# 88LM_Schematic.net
KiCad netlist of a schematic drawn in Altium Designer
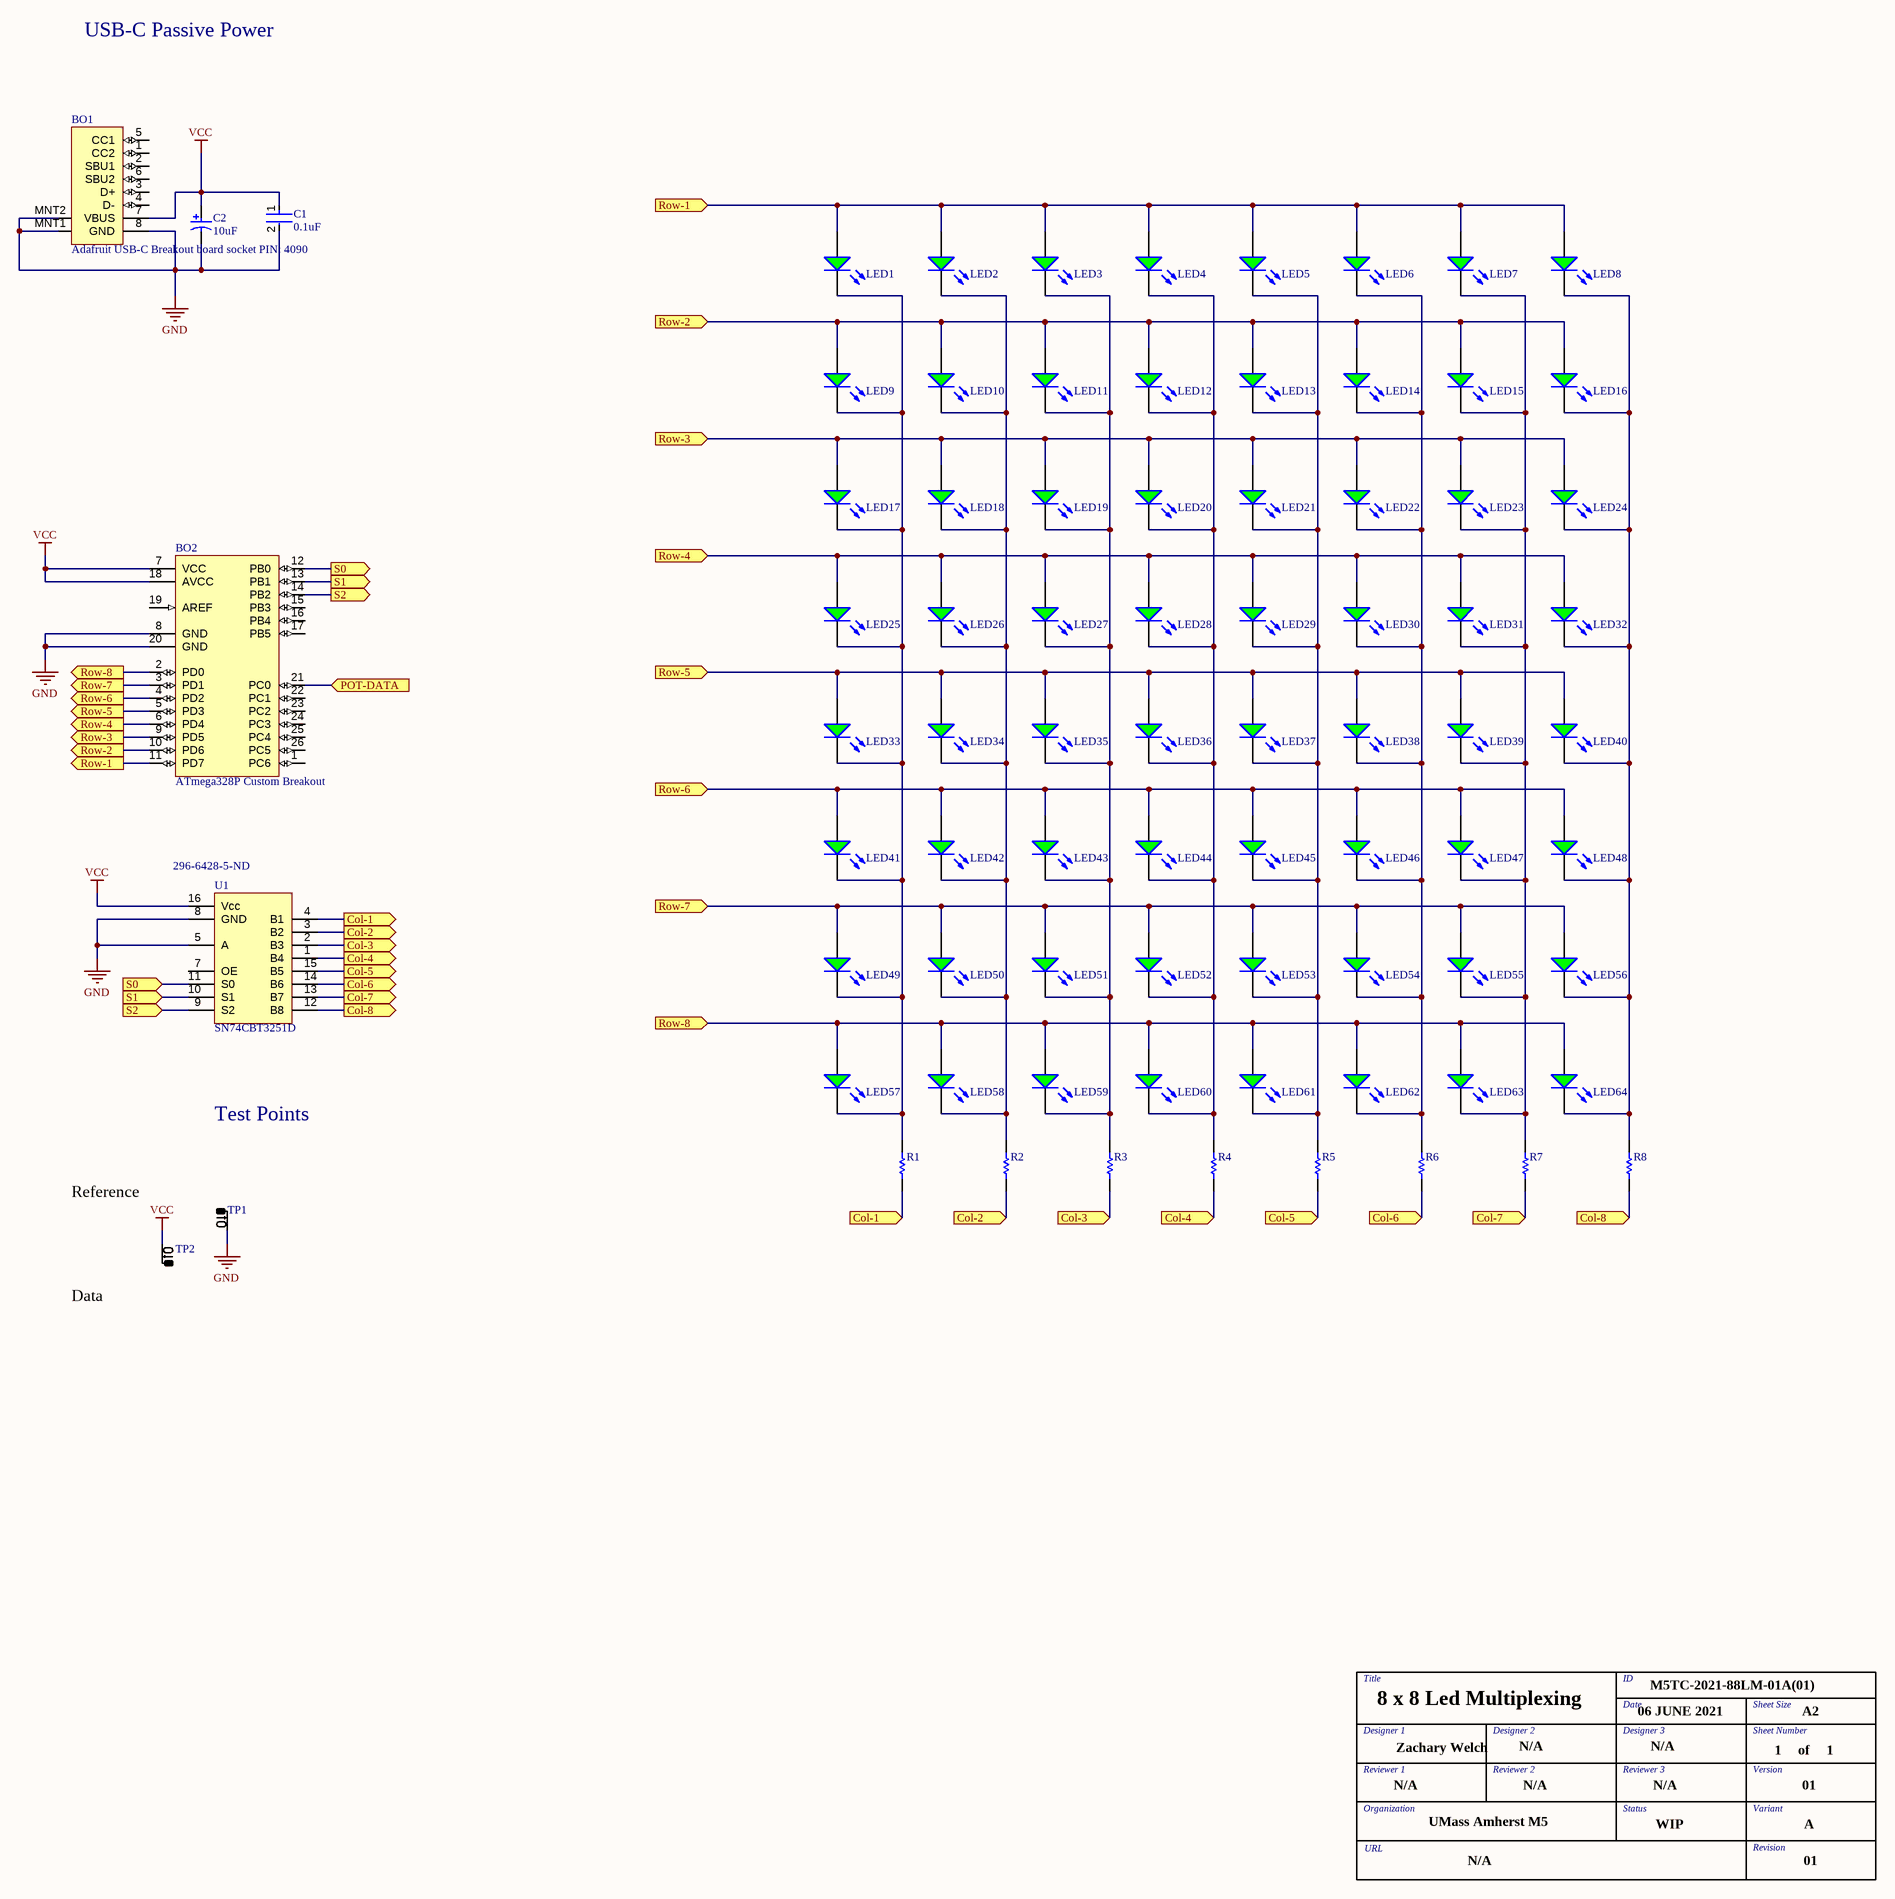
[diagram p0: 88LM Schematic.SchDoc]

(export (version "E")
  (design (tool "Eeschema 10.0.6"))
  (components
    (comp (ref "BO1")
      (value "Adafruit USB-C Breakout board socket PIN: 4090")
      (footprint "Adafruit USB-C Breakout")
      (description "https://www.adafruit.com/product/4090")
      (libsource (lib "Master Schematic Library") (part "Adafruit USB-C Breakout"))
    )
    (comp (ref "BO2")
      (value "ATmega328P Custom Breakout")
      (footprint "328P-BOB")
      (description "Custom Breakout Board for 328P-PU")
      (libsource (lib "Master Schematic Library") (part "328P-BOB"))
    )
    (comp (ref "C1")
      (value "0.1uF")
      (footprint "FP-C0603-CJ-MFG")
      (description "CAP CER 0.1UF 50V X7R 0603")
      (fields (field (name "MANUFACTURER PART NUMBER") "C0603X104K5RACTU") (field (name "VOLTAGE") "50V"))
      (libsource (lib "Altium Content Vault") (part "11868f565c42a9108669ba33697ecf6"))
    )
    (comp (ref "C2")
      (value "10uF")
      (footprint "KEMT-A-3216-18-2_M")
      (description "Capacitor, Tantalum, 10 uF, +/- 10%, 10 V, -55 to 125 degC, 2-Pin SMD (1206), RoHS, Tape and Reel")
      (fields (field (name "TOLERANCE") "±10%") (field (name "MANUFACTURER") "Kemet"))
      (libsource (lib "Altium Content Vault") (part "CAP-P-2"))
    )
    (comp (ref "LED1")
      (value "HLMP-4740")
      (footprint "AVAG-HLMP-4740")
      (description "T-1 3/4 (5 mm) Low Current LED Lamp, Green, 1.9 V, -20 to 100 degC, 2-Pin THD, RoHS, Bulk")
      (fields (field (name "MANUFACTURER") "AvagoTechnologies"))
      (libsource (lib "Altium Content Vault") (part "LED-GREEN-AK-2"))
    )
    (comp (ref "LED2")
      (value "HLMP-4740")
      (footprint "AVAG-HLMP-4740")
      (description "T-1 3/4 (5 mm) Low Current LED Lamp, Green, 1.9 V, -20 to 100 degC, 2-Pin THD, RoHS, Bulk")
      (fields (field (name "MANUFACTURER") "AvagoTechnologies"))
      (libsource (lib "Altium Content Vault") (part "LED-GREEN-AK-2"))
    )
    (comp (ref "LED3")
      (value "HLMP-4740")
      (footprint "AVAG-HLMP-4740")
      (description "T-1 3/4 (5 mm) Low Current LED Lamp, Green, 1.9 V, -20 to 100 degC, 2-Pin THD, RoHS, Bulk")
      (fields (field (name "MANUFACTURER") "AvagoTechnologies"))
      (libsource (lib "Altium Content Vault") (part "LED-GREEN-AK-2"))
    )
    (comp (ref "LED4")
      (value "HLMP-4740")
      (footprint "AVAG-HLMP-4740")
      (description "T-1 3/4 (5 mm) Low Current LED Lamp, Green, 1.9 V, -20 to 100 degC, 2-Pin THD, RoHS, Bulk")
      (fields (field (name "MANUFACTURER") "AvagoTechnologies"))
      (libsource (lib "Altium Content Vault") (part "LED-GREEN-AK-2"))
    )
    (comp (ref "LED5")
      (value "HLMP-4740")
      (footprint "AVAG-HLMP-4740")
      (description "T-1 3/4 (5 mm) Low Current LED Lamp, Green, 1.9 V, -20 to 100 degC, 2-Pin THD, RoHS, Bulk")
      (fields (field (name "MANUFACTURER") "AvagoTechnologies"))
      (libsource (lib "Altium Content Vault") (part "LED-GREEN-AK-2"))
    )
    (comp (ref "LED6")
      (value "HLMP-4740")
      (footprint "AVAG-HLMP-4740")
      (description "T-1 3/4 (5 mm) Low Current LED Lamp, Green, 1.9 V, -20 to 100 degC, 2-Pin THD, RoHS, Bulk")
      (fields (field (name "MANUFACTURER") "AvagoTechnologies"))
      (libsource (lib "Altium Content Vault") (part "LED-GREEN-AK-2"))
    )
    (comp (ref "LED7")
      (value "HLMP-4740")
      (footprint "AVAG-HLMP-4740")
      (description "T-1 3/4 (5 mm) Low Current LED Lamp, Green, 1.9 V, -20 to 100 degC, 2-Pin THD, RoHS, Bulk")
      (fields (field (name "MANUFACTURER") "AvagoTechnologies"))
      (libsource (lib "Altium Content Vault") (part "LED-GREEN-AK-2"))
    )
    (comp (ref "LED8")
      (value "HLMP-4740")
      (footprint "AVAG-HLMP-4740")
      (description "T-1 3/4 (5 mm) Low Current LED Lamp, Green, 1.9 V, -20 to 100 degC, 2-Pin THD, RoHS, Bulk")
      (fields (field (name "MANUFACTURER") "AvagoTechnologies"))
      (libsource (lib "Altium Content Vault") (part "LED-GREEN-AK-2"))
    )
    (comp (ref "LED9")
      (value "HLMP-4740")
      (footprint "AVAG-HLMP-4740")
      (description "T-1 3/4 (5 mm) Low Current LED Lamp, Green, 1.9 V, -20 to 100 degC, 2-Pin THD, RoHS, Bulk")
      (fields (field (name "MANUFACTURER") "AvagoTechnologies"))
      (libsource (lib "Altium Content Vault") (part "LED-GREEN-AK-2"))
    )
    (comp (ref "LED10")
      (value "HLMP-4740")
      (footprint "AVAG-HLMP-4740")
      (description "T-1 3/4 (5 mm) Low Current LED Lamp, Green, 1.9 V, -20 to 100 degC, 2-Pin THD, RoHS, Bulk")
      (fields (field (name "MANUFACTURER") "AvagoTechnologies"))
      (libsource (lib "Altium Content Vault") (part "LED-GREEN-AK-2"))
    )
    (comp (ref "LED11")
      (value "HLMP-4740")
      (footprint "AVAG-HLMP-4740")
      (description "T-1 3/4 (5 mm) Low Current LED Lamp, Green, 1.9 V, -20 to 100 degC, 2-Pin THD, RoHS, Bulk")
      (fields (field (name "MANUFACTURER") "AvagoTechnologies"))
      (libsource (lib "Altium Content Vault") (part "LED-GREEN-AK-2"))
    )
    (comp (ref "LED12")
      (value "HLMP-4740")
      (footprint "AVAG-HLMP-4740")
      (description "T-1 3/4 (5 mm) Low Current LED Lamp, Green, 1.9 V, -20 to 100 degC, 2-Pin THD, RoHS, Bulk")
      (fields (field (name "MANUFACTURER") "AvagoTechnologies"))
      (libsource (lib "Altium Content Vault") (part "LED-GREEN-AK-2"))
    )
    (comp (ref "LED13")
      (value "HLMP-4740")
      (footprint "AVAG-HLMP-4740")
      (description "T-1 3/4 (5 mm) Low Current LED Lamp, Green, 1.9 V, -20 to 100 degC, 2-Pin THD, RoHS, Bulk")
      (fields (field (name "MANUFACTURER") "AvagoTechnologies"))
      (libsource (lib "Altium Content Vault") (part "LED-GREEN-AK-2"))
    )
    (comp (ref "LED14")
      (value "HLMP-4740")
      (footprint "AVAG-HLMP-4740")
      (description "T-1 3/4 (5 mm) Low Current LED Lamp, Green, 1.9 V, -20 to 100 degC, 2-Pin THD, RoHS, Bulk")
      (fields (field (name "MANUFACTURER") "AvagoTechnologies"))
      (libsource (lib "Altium Content Vault") (part "LED-GREEN-AK-2"))
    )
    (comp (ref "LED15")
      (value "HLMP-4740")
      (footprint "AVAG-HLMP-4740")
      (description "T-1 3/4 (5 mm) Low Current LED Lamp, Green, 1.9 V, -20 to 100 degC, 2-Pin THD, RoHS, Bulk")
      (fields (field (name "MANUFACTURER") "AvagoTechnologies"))
      (libsource (lib "Altium Content Vault") (part "LED-GREEN-AK-2"))
    )
    (comp (ref "LED16")
      (value "HLMP-4740")
      (footprint "AVAG-HLMP-4740")
      (description "T-1 3/4 (5 mm) Low Current LED Lamp, Green, 1.9 V, -20 to 100 degC, 2-Pin THD, RoHS, Bulk")
      (fields (field (name "MANUFACTURER") "AvagoTechnologies"))
      (libsource (lib "Altium Content Vault") (part "LED-GREEN-AK-2"))
    )
    (comp (ref "LED17")
      (value "HLMP-4740")
      (footprint "AVAG-HLMP-4740")
      (description "T-1 3/4 (5 mm) Low Current LED Lamp, Green, 1.9 V, -20 to 100 degC, 2-Pin THD, RoHS, Bulk")
      (fields (field (name "MANUFACTURER") "AvagoTechnologies"))
      (libsource (lib "Altium Content Vault") (part "LED-GREEN-AK-2"))
    )
    (comp (ref "LED18")
      (value "HLMP-4740")
      (footprint "AVAG-HLMP-4740")
      (description "T-1 3/4 (5 mm) Low Current LED Lamp, Green, 1.9 V, -20 to 100 degC, 2-Pin THD, RoHS, Bulk")
      (fields (field (name "MANUFACTURER") "AvagoTechnologies"))
      (libsource (lib "Altium Content Vault") (part "LED-GREEN-AK-2"))
    )
    (comp (ref "LED19")
      (value "HLMP-4740")
      (footprint "AVAG-HLMP-4740")
      (description "T-1 3/4 (5 mm) Low Current LED Lamp, Green, 1.9 V, -20 to 100 degC, 2-Pin THD, RoHS, Bulk")
      (fields (field (name "MANUFACTURER") "AvagoTechnologies"))
      (libsource (lib "Altium Content Vault") (part "LED-GREEN-AK-2"))
    )
    (comp (ref "LED20")
      (value "HLMP-4740")
      (footprint "AVAG-HLMP-4740")
      (description "T-1 3/4 (5 mm) Low Current LED Lamp, Green, 1.9 V, -20 to 100 degC, 2-Pin THD, RoHS, Bulk")
      (fields (field (name "MANUFACTURER") "AvagoTechnologies"))
      (libsource (lib "Altium Content Vault") (part "LED-GREEN-AK-2"))
    )
    (comp (ref "LED21")
      (value "HLMP-4740")
      (footprint "AVAG-HLMP-4740")
      (description "T-1 3/4 (5 mm) Low Current LED Lamp, Green, 1.9 V, -20 to 100 degC, 2-Pin THD, RoHS, Bulk")
      (fields (field (name "MANUFACTURER") "AvagoTechnologies"))
      (libsource (lib "Altium Content Vault") (part "LED-GREEN-AK-2"))
    )
    (comp (ref "LED22")
      (value "HLMP-4740")
      (footprint "AVAG-HLMP-4740")
      (description "T-1 3/4 (5 mm) Low Current LED Lamp, Green, 1.9 V, -20 to 100 degC, 2-Pin THD, RoHS, Bulk")
      (fields (field (name "MANUFACTURER") "AvagoTechnologies"))
      (libsource (lib "Altium Content Vault") (part "LED-GREEN-AK-2"))
    )
    (comp (ref "LED23")
      (value "HLMP-4740")
      (footprint "AVAG-HLMP-4740")
      (description "T-1 3/4 (5 mm) Low Current LED Lamp, Green, 1.9 V, -20 to 100 degC, 2-Pin THD, RoHS, Bulk")
      (fields (field (name "MANUFACTURER") "AvagoTechnologies"))
      (libsource (lib "Altium Content Vault") (part "LED-GREEN-AK-2"))
    )
    (comp (ref "LED24")
      (value "HLMP-4740")
      (footprint "AVAG-HLMP-4740")
      (description "T-1 3/4 (5 mm) Low Current LED Lamp, Green, 1.9 V, -20 to 100 degC, 2-Pin THD, RoHS, Bulk")
      (fields (field (name "MANUFACTURER") "AvagoTechnologies"))
      (libsource (lib "Altium Content Vault") (part "LED-GREEN-AK-2"))
    )
    (comp (ref "LED25")
      (value "HLMP-4740")
      (footprint "AVAG-HLMP-4740")
      (description "T-1 3/4 (5 mm) Low Current LED Lamp, Green, 1.9 V, -20 to 100 degC, 2-Pin THD, RoHS, Bulk")
      (fields (field (name "MANUFACTURER") "AvagoTechnologies"))
      (libsource (lib "Altium Content Vault") (part "LED-GREEN-AK-2"))
    )
    (comp (ref "LED26")
      (value "HLMP-4740")
      (footprint "AVAG-HLMP-4740")
      (description "T-1 3/4 (5 mm) Low Current LED Lamp, Green, 1.9 V, -20 to 100 degC, 2-Pin THD, RoHS, Bulk")
      (fields (field (name "MANUFACTURER") "AvagoTechnologies"))
      (libsource (lib "Altium Content Vault") (part "LED-GREEN-AK-2"))
    )
    (comp (ref "LED27")
      (value "HLMP-4740")
      (footprint "AVAG-HLMP-4740")
      (description "T-1 3/4 (5 mm) Low Current LED Lamp, Green, 1.9 V, -20 to 100 degC, 2-Pin THD, RoHS, Bulk")
      (fields (field (name "MANUFACTURER") "AvagoTechnologies"))
      (libsource (lib "Altium Content Vault") (part "LED-GREEN-AK-2"))
    )
    (comp (ref "LED28")
      (value "HLMP-4740")
      (footprint "AVAG-HLMP-4740")
      (description "T-1 3/4 (5 mm) Low Current LED Lamp, Green, 1.9 V, -20 to 100 degC, 2-Pin THD, RoHS, Bulk")
      (fields (field (name "MANUFACTURER") "AvagoTechnologies"))
      (libsource (lib "Altium Content Vault") (part "LED-GREEN-AK-2"))
    )
    (comp (ref "LED29")
      (value "HLMP-4740")
      (footprint "AVAG-HLMP-4740")
      (description "T-1 3/4 (5 mm) Low Current LED Lamp, Green, 1.9 V, -20 to 100 degC, 2-Pin THD, RoHS, Bulk")
      (fields (field (name "MANUFACTURER") "AvagoTechnologies"))
      (libsource (lib "Altium Content Vault") (part "LED-GREEN-AK-2"))
    )
    (comp (ref "LED30")
      (value "HLMP-4740")
      (footprint "AVAG-HLMP-4740")
      (description "T-1 3/4 (5 mm) Low Current LED Lamp, Green, 1.9 V, -20 to 100 degC, 2-Pin THD, RoHS, Bulk")
      (fields (field (name "MANUFACTURER") "AvagoTechnologies"))
      (libsource (lib "Altium Content Vault") (part "LED-GREEN-AK-2"))
    )
    (comp (ref "LED31")
      (value "HLMP-4740")
      (footprint "AVAG-HLMP-4740")
      (description "T-1 3/4 (5 mm) Low Current LED Lamp, Green, 1.9 V, -20 to 100 degC, 2-Pin THD, RoHS, Bulk")
      (fields (field (name "MANUFACTURER") "AvagoTechnologies"))
      (libsource (lib "Altium Content Vault") (part "LED-GREEN-AK-2"))
    )
    (comp (ref "LED32")
      (value "HLMP-4740")
      (footprint "AVAG-HLMP-4740")
      (description "T-1 3/4 (5 mm) Low Current LED Lamp, Green, 1.9 V, -20 to 100 degC, 2-Pin THD, RoHS, Bulk")
      (fields (field (name "MANUFACTURER") "AvagoTechnologies"))
      (libsource (lib "Altium Content Vault") (part "LED-GREEN-AK-2"))
    )
    (comp (ref "LED33")
      (value "HLMP-4740")
      (footprint "AVAG-HLMP-4740")
      (description "T-1 3/4 (5 mm) Low Current LED Lamp, Green, 1.9 V, -20 to 100 degC, 2-Pin THD, RoHS, Bulk")
      (fields (field (name "MANUFACTURER") "AvagoTechnologies"))
      (libsource (lib "Altium Content Vault") (part "LED-GREEN-AK-2"))
    )
    (comp (ref "LED34")
      (value "HLMP-4740")
      (footprint "AVAG-HLMP-4740")
      (description "T-1 3/4 (5 mm) Low Current LED Lamp, Green, 1.9 V, -20 to 100 degC, 2-Pin THD, RoHS, Bulk")
      (fields (field (name "MANUFACTURER") "AvagoTechnologies"))
      (libsource (lib "Altium Content Vault") (part "LED-GREEN-AK-2"))
    )
    (comp (ref "LED35")
      (value "HLMP-4740")
      (footprint "AVAG-HLMP-4740")
      (description "T-1 3/4 (5 mm) Low Current LED Lamp, Green, 1.9 V, -20 to 100 degC, 2-Pin THD, RoHS, Bulk")
      (fields (field (name "MANUFACTURER") "AvagoTechnologies"))
      (libsource (lib "Altium Content Vault") (part "LED-GREEN-AK-2"))
    )
    (comp (ref "LED36")
      (value "HLMP-4740")
      (footprint "AVAG-HLMP-4740")
      (description "T-1 3/4 (5 mm) Low Current LED Lamp, Green, 1.9 V, -20 to 100 degC, 2-Pin THD, RoHS, Bulk")
      (fields (field (name "MANUFACTURER") "AvagoTechnologies"))
      (libsource (lib "Altium Content Vault") (part "LED-GREEN-AK-2"))
    )
    (comp (ref "LED37")
      (value "HLMP-4740")
      (footprint "AVAG-HLMP-4740")
      (description "T-1 3/4 (5 mm) Low Current LED Lamp, Green, 1.9 V, -20 to 100 degC, 2-Pin THD, RoHS, Bulk")
      (fields (field (name "MANUFACTURER") "AvagoTechnologies"))
      (libsource (lib "Altium Content Vault") (part "LED-GREEN-AK-2"))
    )
    (comp (ref "LED38")
      (value "HLMP-4740")
      (footprint "AVAG-HLMP-4740")
      (description "T-1 3/4 (5 mm) Low Current LED Lamp, Green, 1.9 V, -20 to 100 degC, 2-Pin THD, RoHS, Bulk")
      (fields (field (name "MANUFACTURER") "AvagoTechnologies"))
      (libsource (lib "Altium Content Vault") (part "LED-GREEN-AK-2"))
    )
    (comp (ref "LED39")
      (value "HLMP-4740")
      (footprint "AVAG-HLMP-4740")
      (description "T-1 3/4 (5 mm) Low Current LED Lamp, Green, 1.9 V, -20 to 100 degC, 2-Pin THD, RoHS, Bulk")
      (fields (field (name "MANUFACTURER") "AvagoTechnologies"))
      (libsource (lib "Altium Content Vault") (part "LED-GREEN-AK-2"))
    )
    (comp (ref "LED40")
      (value "HLMP-4740")
      (footprint "AVAG-HLMP-4740")
      (description "T-1 3/4 (5 mm) Low Current LED Lamp, Green, 1.9 V, -20 to 100 degC, 2-Pin THD, RoHS, Bulk")
      (fields (field (name "MANUFACTURER") "AvagoTechnologies"))
      (libsource (lib "Altium Content Vault") (part "LED-GREEN-AK-2"))
    )
    (comp (ref "LED41")
      (value "HLMP-4740")
      (footprint "AVAG-HLMP-4740")
      (description "T-1 3/4 (5 mm) Low Current LED Lamp, Green, 1.9 V, -20 to 100 degC, 2-Pin THD, RoHS, Bulk")
      (fields (field (name "MANUFACTURER") "AvagoTechnologies"))
      (libsource (lib "Altium Content Vault") (part "LED-GREEN-AK-2"))
    )
    (comp (ref "LED42")
      (value "HLMP-4740")
      (footprint "AVAG-HLMP-4740")
      (description "T-1 3/4 (5 mm) Low Current LED Lamp, Green, 1.9 V, -20 to 100 degC, 2-Pin THD, RoHS, Bulk")
      (fields (field (name "MANUFACTURER") "AvagoTechnologies"))
      (libsource (lib "Altium Content Vault") (part "LED-GREEN-AK-2"))
    )
    (comp (ref "LED43")
      (value "HLMP-4740")
      (footprint "AVAG-HLMP-4740")
      (description "T-1 3/4 (5 mm) Low Current LED Lamp, Green, 1.9 V, -20 to 100 degC, 2-Pin THD, RoHS, Bulk")
      (fields (field (name "MANUFACTURER") "AvagoTechnologies"))
      (libsource (lib "Altium Content Vault") (part "LED-GREEN-AK-2"))
    )
    (comp (ref "LED44")
      (value "HLMP-4740")
      (footprint "AVAG-HLMP-4740")
      (description "T-1 3/4 (5 mm) Low Current LED Lamp, Green, 1.9 V, -20 to 100 degC, 2-Pin THD, RoHS, Bulk")
      (fields (field (name "MANUFACTURER") "AvagoTechnologies"))
      (libsource (lib "Altium Content Vault") (part "LED-GREEN-AK-2"))
    )
    (comp (ref "LED45")
      (value "HLMP-4740")
      (footprint "AVAG-HLMP-4740")
      (description "T-1 3/4 (5 mm) Low Current LED Lamp, Green, 1.9 V, -20 to 100 degC, 2-Pin THD, RoHS, Bulk")
      (fields (field (name "MANUFACTURER") "AvagoTechnologies"))
      (libsource (lib "Altium Content Vault") (part "LED-GREEN-AK-2"))
    )
    (comp (ref "LED46")
      (value "HLMP-4740")
      (footprint "AVAG-HLMP-4740")
      (description "T-1 3/4 (5 mm) Low Current LED Lamp, Green, 1.9 V, -20 to 100 degC, 2-Pin THD, RoHS, Bulk")
      (fields (field (name "MANUFACTURER") "AvagoTechnologies"))
      (libsource (lib "Altium Content Vault") (part "LED-GREEN-AK-2"))
    )
    (comp (ref "LED47")
      (value "HLMP-4740")
      (footprint "AVAG-HLMP-4740")
      (description "T-1 3/4 (5 mm) Low Current LED Lamp, Green, 1.9 V, -20 to 100 degC, 2-Pin THD, RoHS, Bulk")
      (fields (field (name "MANUFACTURER") "AvagoTechnologies"))
      (libsource (lib "Altium Content Vault") (part "LED-GREEN-AK-2"))
    )
    (comp (ref "LED48")
      (value "HLMP-4740")
      (footprint "AVAG-HLMP-4740")
      (description "T-1 3/4 (5 mm) Low Current LED Lamp, Green, 1.9 V, -20 to 100 degC, 2-Pin THD, RoHS, Bulk")
      (fields (field (name "MANUFACTURER") "AvagoTechnologies"))
      (libsource (lib "Altium Content Vault") (part "LED-GREEN-AK-2"))
    )
    (comp (ref "LED49")
      (value "HLMP-4740")
      (footprint "AVAG-HLMP-4740")
      (description "T-1 3/4 (5 mm) Low Current LED Lamp, Green, 1.9 V, -20 to 100 degC, 2-Pin THD, RoHS, Bulk")
      (fields (field (name "MANUFACTURER") "AvagoTechnologies"))
      (libsource (lib "Altium Content Vault") (part "LED-GREEN-AK-2"))
    )
    (comp (ref "LED50")
      (value "HLMP-4740")
      (footprint "AVAG-HLMP-4740")
      (description "T-1 3/4 (5 mm) Low Current LED Lamp, Green, 1.9 V, -20 to 100 degC, 2-Pin THD, RoHS, Bulk")
      (fields (field (name "MANUFACTURER") "AvagoTechnologies"))
      (libsource (lib "Altium Content Vault") (part "LED-GREEN-AK-2"))
    )
    (comp (ref "LED51")
      (value "HLMP-4740")
      (footprint "AVAG-HLMP-4740")
      (description "T-1 3/4 (5 mm) Low Current LED Lamp, Green, 1.9 V, -20 to 100 degC, 2-Pin THD, RoHS, Bulk")
      (fields (field (name "MANUFACTURER") "AvagoTechnologies"))
      (libsource (lib "Altium Content Vault") (part "LED-GREEN-AK-2"))
    )
    (comp (ref "LED52")
      (value "HLMP-4740")
      (footprint "AVAG-HLMP-4740")
      (description "T-1 3/4 (5 mm) Low Current LED Lamp, Green, 1.9 V, -20 to 100 degC, 2-Pin THD, RoHS, Bulk")
      (fields (field (name "MANUFACTURER") "AvagoTechnologies"))
      (libsource (lib "Altium Content Vault") (part "LED-GREEN-AK-2"))
    )
    (comp (ref "LED53")
      (value "HLMP-4740")
      (footprint "AVAG-HLMP-4740")
      (description "T-1 3/4 (5 mm) Low Current LED Lamp, Green, 1.9 V, -20 to 100 degC, 2-Pin THD, RoHS, Bulk")
      (fields (field (name "MANUFACTURER") "AvagoTechnologies"))
      (libsource (lib "Altium Content Vault") (part "LED-GREEN-AK-2"))
    )
    (comp (ref "LED54")
      (value "HLMP-4740")
      (footprint "AVAG-HLMP-4740")
      (description "T-1 3/4 (5 mm) Low Current LED Lamp, Green, 1.9 V, -20 to 100 degC, 2-Pin THD, RoHS, Bulk")
      (fields (field (name "MANUFACTURER") "AvagoTechnologies"))
      (libsource (lib "Altium Content Vault") (part "LED-GREEN-AK-2"))
    )
    (comp (ref "LED55")
      (value "HLMP-4740")
      (footprint "AVAG-HLMP-4740")
      (description "T-1 3/4 (5 mm) Low Current LED Lamp, Green, 1.9 V, -20 to 100 degC, 2-Pin THD, RoHS, Bulk")
      (fields (field (name "MANUFACTURER") "AvagoTechnologies"))
      (libsource (lib "Altium Content Vault") (part "LED-GREEN-AK-2"))
    )
    (comp (ref "LED56")
      (value "HLMP-4740")
      (footprint "AVAG-HLMP-4740")
      (description "T-1 3/4 (5 mm) Low Current LED Lamp, Green, 1.9 V, -20 to 100 degC, 2-Pin THD, RoHS, Bulk")
      (fields (field (name "MANUFACTURER") "AvagoTechnologies"))
      (libsource (lib "Altium Content Vault") (part "LED-GREEN-AK-2"))
    )
    (comp (ref "LED57")
      (value "HLMP-4740")
      (footprint "AVAG-HLMP-4740")
      (description "T-1 3/4 (5 mm) Low Current LED Lamp, Green, 1.9 V, -20 to 100 degC, 2-Pin THD, RoHS, Bulk")
      (fields (field (name "MANUFACTURER") "AvagoTechnologies"))
      (libsource (lib "Altium Content Vault") (part "LED-GREEN-AK-2"))
    )
    (comp (ref "LED58")
      (value "HLMP-4740")
      (footprint "AVAG-HLMP-4740")
      (description "T-1 3/4 (5 mm) Low Current LED Lamp, Green, 1.9 V, -20 to 100 degC, 2-Pin THD, RoHS, Bulk")
      (fields (field (name "MANUFACTURER") "AvagoTechnologies"))
      (libsource (lib "Altium Content Vault") (part "LED-GREEN-AK-2"))
    )
    (comp (ref "LED59")
      (value "HLMP-4740")
      (footprint "AVAG-HLMP-4740")
      (description "T-1 3/4 (5 mm) Low Current LED Lamp, Green, 1.9 V, -20 to 100 degC, 2-Pin THD, RoHS, Bulk")
      (fields (field (name "MANUFACTURER") "AvagoTechnologies"))
      (libsource (lib "Altium Content Vault") (part "LED-GREEN-AK-2"))
    )
    (comp (ref "LED60")
      (value "HLMP-4740")
      (footprint "AVAG-HLMP-4740")
      (description "T-1 3/4 (5 mm) Low Current LED Lamp, Green, 1.9 V, -20 to 100 degC, 2-Pin THD, RoHS, Bulk")
      (fields (field (name "MANUFACTURER") "AvagoTechnologies"))
      (libsource (lib "Altium Content Vault") (part "LED-GREEN-AK-2"))
    )
    (comp (ref "LED61")
      (value "HLMP-4740")
      (footprint "AVAG-HLMP-4740")
      (description "T-1 3/4 (5 mm) Low Current LED Lamp, Green, 1.9 V, -20 to 100 degC, 2-Pin THD, RoHS, Bulk")
      (fields (field (name "MANUFACTURER") "AvagoTechnologies"))
      (libsource (lib "Altium Content Vault") (part "LED-GREEN-AK-2"))
    )
    (comp (ref "LED62")
      (value "HLMP-4740")
      (footprint "AVAG-HLMP-4740")
      (description "T-1 3/4 (5 mm) Low Current LED Lamp, Green, 1.9 V, -20 to 100 degC, 2-Pin THD, RoHS, Bulk")
      (fields (field (name "MANUFACTURER") "AvagoTechnologies"))
      (libsource (lib "Altium Content Vault") (part "LED-GREEN-AK-2"))
    )
    (comp (ref "LED63")
      (value "HLMP-4740")
      (footprint "AVAG-HLMP-4740")
      (description "T-1 3/4 (5 mm) Low Current LED Lamp, Green, 1.9 V, -20 to 100 degC, 2-Pin THD, RoHS, Bulk")
      (fields (field (name "MANUFACTURER") "AvagoTechnologies"))
      (libsource (lib "Altium Content Vault") (part "LED-GREEN-AK-2"))
    )
    (comp (ref "LED64")
      (value "HLMP-4740")
      (footprint "AVAG-HLMP-4740")
      (description "T-1 3/4 (5 mm) Low Current LED Lamp, Green, 1.9 V, -20 to 100 degC, 2-Pin THD, RoHS, Bulk")
      (fields (field (name "MANUFACTURER") "AvagoTechnologies"))
      (libsource (lib "Altium Content Vault") (part "LED-GREEN-AK-2"))
    )
    (comp (ref "R1")
      (value "ERJ-6GEYJ201V")
      (footprint "RESC2013X70X40ML20T20")
      (fields (field (name "MANUFACTURER") "Panasonic"))
      (libsource (lib "Altium Content Vault") (part "RES"))
    )
    (comp (ref "R2")
      (value "ERJ-6GEYJ201V")
      (footprint "RESC2013X70X40ML20T20")
      (fields (field (name "MANUFACTURER") "Panasonic"))
      (libsource (lib "Altium Content Vault") (part "RES"))
    )
    (comp (ref "R3")
      (value "ERJ-6GEYJ201V")
      (footprint "RESC2013X70X40ML20T20")
      (fields (field (name "MANUFACTURER") "Panasonic"))
      (libsource (lib "Altium Content Vault") (part "RES"))
    )
    (comp (ref "R4")
      (value "ERJ-6GEYJ201V")
      (footprint "RESC2013X70X40ML20T20")
      (fields (field (name "MANUFACTURER") "Panasonic"))
      (libsource (lib "Altium Content Vault") (part "RES"))
    )
    (comp (ref "R5")
      (value "ERJ-6GEYJ201V")
      (footprint "RESC2013X70X40ML20T20")
      (fields (field (name "MANUFACTURER") "Panasonic"))
      (libsource (lib "Altium Content Vault") (part "RES"))
    )
    (comp (ref "R6")
      (value "ERJ-6GEYJ201V")
      (footprint "RESC2013X70X40ML20T20")
      (fields (field (name "MANUFACTURER") "Panasonic"))
      (libsource (lib "Altium Content Vault") (part "RES"))
    )
    (comp (ref "R7")
      (value "ERJ-6GEYJ201V")
      (footprint "RESC2013X70X40ML20T20")
      (fields (field (name "MANUFACTURER") "Panasonic"))
      (libsource (lib "Altium Content Vault") (part "RES"))
    )
    (comp (ref "R8")
      (value "ERJ-6GEYJ201V")
      (footprint "RESC2013X70X40ML20T20")
      (fields (field (name "MANUFACTURER") "Panasonic"))
      (libsource (lib "Altium Content Vault") (part "RES"))
    )
    (comp (ref "Tb") (value "Title Block") (libsource (lib "Master Schematic Library") (part "Title Block")))
    (comp (ref "TP1")
      (value "Loop post and pad test point")
      (footprint "TEST POINT (LOOP/POST/PAD)")
      (description "Requires 1 Keystone Electronics PC Test Point Multipurpose (see 5011 for example)")
      (libsource (lib "Master Library") (part "Test Point (Loop/Post/Pad)"))
    )
    (comp (ref "TP2")
      (value "Loop post and pad test point")
      (footprint "TEST POINT (LOOP/POST/PAD)")
      (description "Requires 1 Keystone Electronics PC Test Point Multipurpose (see 5011 for example)")
      (libsource (lib "Master Library") (part "Test Point (Loop/Post/Pad)"))
    )
    (comp (ref "U1")
      (value "SN74CBT3251D")
      (footprint "Master PCB Library:SOIC127P600X175-16N")
      (fields (field (name "SUPPLIER PART NUMBER 1") "296-6428-5-ND"))
      (libsource (lib "Master Schematic Library") (part "SN74CBT3251D"))
    )
  )
  (nets
    (net (code "1") (name "/Col-1") (class "Default")
      (node (ref "R1") (pin "1") (pinfunction "1_1") (pintype "passive"))
      (node (ref "U1") (pin "4") (pinfunction "B1_4") (pintype "passive"))
    )
    (net (code "2") (name "/Col-2") (class "Default")
      (node (ref "R2") (pin "1") (pinfunction "1_1") (pintype "passive"))
      (node (ref "U1") (pin "3") (pinfunction "B2_3") (pintype "passive"))
    )
    (net (code "3") (name "/Col-3") (class "Default")
      (node (ref "R3") (pin "1") (pinfunction "1_1") (pintype "passive"))
      (node (ref "U1") (pin "2") (pinfunction "B3_2") (pintype "passive"))
    )
    (net (code "4") (name "/Col-4") (class "Default")
      (node (ref "R4") (pin "1") (pinfunction "1_1") (pintype "passive"))
      (node (ref "U1") (pin "1") (pinfunction "B4_1") (pintype "passive"))
    )
    (net (code "5") (name "/Col-5") (class "Default")
      (node (ref "R5") (pin "1") (pinfunction "1_1") (pintype "passive"))
      (node (ref "U1") (pin "15") (pinfunction "B5_15") (pintype "passive"))
    )
    (net (code "6") (name "/Col-6") (class "Default")
      (node (ref "R6") (pin "1") (pinfunction "1_1") (pintype "passive"))
      (node (ref "U1") (pin "14") (pinfunction "B6_14") (pintype "passive"))
    )
    (net (code "7") (name "/Col-7") (class "Default")
      (node (ref "R7") (pin "1") (pinfunction "1_1") (pintype "passive"))
      (node (ref "U1") (pin "13") (pinfunction "B7_13") (pintype "passive"))
    )
    (net (code "8") (name "/Col-8") (class "Default")
      (node (ref "R8") (pin "1") (pinfunction "1_1") (pintype "passive"))
      (node (ref "U1") (pin "12") (pinfunction "B8_12") (pintype "passive"))
    )
    (net (code "9") (name "/POT-DATA") (class "Default")
      (node (ref "BO2") (pin "21") (pinfunction "PC0_21") (pintype "bidirectional"))
    )
    (net (code "10") (name "/Row-1") (class "Default")
      (node (ref "BO2") (pin "11") (pinfunction "PD7_11") (pintype "bidirectional"))
      (node (ref "LED1") (pin "1") (pinfunction "A_1") (pintype "passive"))
      (node (ref "LED2") (pin "1") (pinfunction "A_1") (pintype "passive"))
      (node (ref "LED3") (pin "1") (pinfunction "A_1") (pintype "passive"))
      (node (ref "LED4") (pin "1") (pinfunction "A_1") (pintype "passive"))
      (node (ref "LED5") (pin "1") (pinfunction "A_1") (pintype "passive"))
      (node (ref "LED6") (pin "1") (pinfunction "A_1") (pintype "passive"))
      (node (ref "LED7") (pin "1") (pinfunction "A_1") (pintype "passive"))
      (node (ref "LED8") (pin "1") (pinfunction "A_1") (pintype "passive"))
    )
    (net (code "11") (name "/Row-2") (class "Default")
      (node (ref "BO2") (pin "10") (pinfunction "PD6_10") (pintype "bidirectional"))
      (node (ref "LED10") (pin "1") (pinfunction "A_1") (pintype "passive"))
      (node (ref "LED11") (pin "1") (pinfunction "A_1") (pintype "passive"))
      (node (ref "LED12") (pin "1") (pinfunction "A_1") (pintype "passive"))
      (node (ref "LED13") (pin "1") (pinfunction "A_1") (pintype "passive"))
      (node (ref "LED14") (pin "1") (pinfunction "A_1") (pintype "passive"))
      (node (ref "LED15") (pin "1") (pinfunction "A_1") (pintype "passive"))
      (node (ref "LED16") (pin "1") (pinfunction "A_1") (pintype "passive"))
      (node (ref "LED9") (pin "1") (pinfunction "A_1") (pintype "passive"))
    )
    (net (code "12") (name "/Row-3") (class "Default")
      (node (ref "BO2") (pin "9") (pinfunction "PD5_9") (pintype "bidirectional"))
      (node (ref "LED17") (pin "1") (pinfunction "A_1") (pintype "passive"))
      (node (ref "LED18") (pin "1") (pinfunction "A_1") (pintype "passive"))
      (node (ref "LED19") (pin "1") (pinfunction "A_1") (pintype "passive"))
      (node (ref "LED20") (pin "1") (pinfunction "A_1") (pintype "passive"))
      (node (ref "LED21") (pin "1") (pinfunction "A_1") (pintype "passive"))
      (node (ref "LED22") (pin "1") (pinfunction "A_1") (pintype "passive"))
      (node (ref "LED23") (pin "1") (pinfunction "A_1") (pintype "passive"))
      (node (ref "LED24") (pin "1") (pinfunction "A_1") (pintype "passive"))
    )
    (net (code "13") (name "/Row-4") (class "Default")
      (node (ref "BO2") (pin "6") (pinfunction "PD4_6") (pintype "bidirectional"))
      (node (ref "LED25") (pin "1") (pinfunction "A_1") (pintype "passive"))
      (node (ref "LED26") (pin "1") (pinfunction "A_1") (pintype "passive"))
      (node (ref "LED27") (pin "1") (pinfunction "A_1") (pintype "passive"))
      (node (ref "LED28") (pin "1") (pinfunction "A_1") (pintype "passive"))
      (node (ref "LED29") (pin "1") (pinfunction "A_1") (pintype "passive"))
      (node (ref "LED30") (pin "1") (pinfunction "A_1") (pintype "passive"))
      (node (ref "LED31") (pin "1") (pinfunction "A_1") (pintype "passive"))
      (node (ref "LED32") (pin "1") (pinfunction "A_1") (pintype "passive"))
    )
    (net (code "14") (name "/Row-5") (class "Default")
      (node (ref "BO2") (pin "5") (pinfunction "PD3_5") (pintype "bidirectional"))
      (node (ref "LED33") (pin "1") (pinfunction "A_1") (pintype "passive"))
      (node (ref "LED34") (pin "1") (pinfunction "A_1") (pintype "passive"))
      (node (ref "LED35") (pin "1") (pinfunction "A_1") (pintype "passive"))
      (node (ref "LED36") (pin "1") (pinfunction "A_1") (pintype "passive"))
      (node (ref "LED37") (pin "1") (pinfunction "A_1") (pintype "passive"))
      (node (ref "LED38") (pin "1") (pinfunction "A_1") (pintype "passive"))
      (node (ref "LED39") (pin "1") (pinfunction "A_1") (pintype "passive"))
      (node (ref "LED40") (pin "1") (pinfunction "A_1") (pintype "passive"))
    )
    (net (code "15") (name "/Row-6") (class "Default")
      (node (ref "BO2") (pin "4") (pinfunction "PD2_4") (pintype "bidirectional"))
      (node (ref "LED41") (pin "1") (pinfunction "A_1") (pintype "passive"))
      (node (ref "LED42") (pin "1") (pinfunction "A_1") (pintype "passive"))
      (node (ref "LED43") (pin "1") (pinfunction "A_1") (pintype "passive"))
      (node (ref "LED44") (pin "1") (pinfunction "A_1") (pintype "passive"))
      (node (ref "LED45") (pin "1") (pinfunction "A_1") (pintype "passive"))
      (node (ref "LED46") (pin "1") (pinfunction "A_1") (pintype "passive"))
      (node (ref "LED47") (pin "1") (pinfunction "A_1") (pintype "passive"))
      (node (ref "LED48") (pin "1") (pinfunction "A_1") (pintype "passive"))
    )
    (net (code "16") (name "/Row-7") (class "Default")
      (node (ref "BO2") (pin "3") (pinfunction "PD1_3") (pintype "bidirectional"))
      (node (ref "LED49") (pin "1") (pinfunction "A_1") (pintype "passive"))
      (node (ref "LED50") (pin "1") (pinfunction "A_1") (pintype "passive"))
      (node (ref "LED51") (pin "1") (pinfunction "A_1") (pintype "passive"))
      (node (ref "LED52") (pin "1") (pinfunction "A_1") (pintype "passive"))
      (node (ref "LED53") (pin "1") (pinfunction "A_1") (pintype "passive"))
      (node (ref "LED54") (pin "1") (pinfunction "A_1") (pintype "passive"))
      (node (ref "LED55") (pin "1") (pinfunction "A_1") (pintype "passive"))
      (node (ref "LED56") (pin "1") (pinfunction "A_1") (pintype "passive"))
    )
    (net (code "17") (name "/Row-8") (class "Default")
      (node (ref "BO2") (pin "2") (pinfunction "PD0_2") (pintype "bidirectional"))
      (node (ref "LED57") (pin "1") (pinfunction "A_1") (pintype "passive"))
      (node (ref "LED58") (pin "1") (pinfunction "A_1") (pintype "passive"))
      (node (ref "LED59") (pin "1") (pinfunction "A_1") (pintype "passive"))
      (node (ref "LED60") (pin "1") (pinfunction "A_1") (pintype "passive"))
      (node (ref "LED61") (pin "1") (pinfunction "A_1") (pintype "passive"))
      (node (ref "LED62") (pin "1") (pinfunction "A_1") (pintype "passive"))
      (node (ref "LED63") (pin "1") (pinfunction "A_1") (pintype "passive"))
      (node (ref "LED64") (pin "1") (pinfunction "A_1") (pintype "passive"))
    )
    (net (code "18") (name "/S0") (class "Default")
      (node (ref "BO2") (pin "12") (pinfunction "PB0_12") (pintype "bidirectional"))
      (node (ref "U1") (pin "11") (pinfunction "S0_11") (pintype "passive"))
    )
    (net (code "19") (name "/S1") (class "Default")
      (node (ref "BO2") (pin "13") (pinfunction "PB1_13") (pintype "bidirectional"))
      (node (ref "U1") (pin "10") (pinfunction "S1_10") (pintype "passive"))
    )
    (net (code "20") (name "/S2") (class "Default")
      (node (ref "BO2") (pin "14") (pinfunction "PB2_14") (pintype "bidirectional"))
      (node (ref "U1") (pin "9") (pinfunction "S2_9") (pintype "passive"))
    )
    (net (code "21") (name "GND") (class "Default")
      (node (ref "BO1") (pin "8") (pinfunction "GND_8") (pintype "power_in"))
      (node (ref "BO1") (pin "MNT1") (pinfunction "MNT1_MNT1") (pintype "passive"))
      (node (ref "BO1") (pin "MNT2") (pinfunction "MNT2_MNT2") (pintype "passive"))
      (node (ref "BO2") (pin "20") (pinfunction "GND_20") (pintype "power_in"))
      (node (ref "BO2") (pin "8") (pinfunction "GND_8") (pintype "power_in"))
      (node (ref "C1") (pin "2") (pinfunction "2_2") (pintype "passive"))
      (node (ref "C2") (pin "2") (pinfunction "2_2") (pintype "passive"))
      (node (ref "TP1") (pin "1") (pinfunction "1_1") (pintype "passive"))
      (node (ref "U1") (pin "5") (pinfunction "A_5") (pintype "passive"))
      (node (ref "U1") (pin "8") (pinfunction "GND_8") (pintype "passive"))
    )
    (net (code "22") (name "Net-(LED1-K)") (class "Default")
      (node (ref "LED1") (pin "2") (pinfunction "K_2") (pintype "passive"))
      (node (ref "LED17") (pin "2") (pinfunction "K_2") (pintype "passive"))
      (node (ref "LED25") (pin "2") (pinfunction "K_2") (pintype "passive"))
      (node (ref "LED33") (pin "2") (pinfunction "K_2") (pintype "passive"))
      (node (ref "LED41") (pin "2") (pinfunction "K_2") (pintype "passive"))
      (node (ref "LED49") (pin "2") (pinfunction "K_2") (pintype "passive"))
      (node (ref "LED57") (pin "2") (pinfunction "K_2") (pintype "passive"))
      (node (ref "LED9") (pin "2") (pinfunction "K_2") (pintype "passive"))
      (node (ref "R1") (pin "2") (pinfunction "2_2") (pintype "passive"))
    )
    (net (code "23") (name "Net-(LED10-K)") (class "Default")
      (node (ref "LED10") (pin "2") (pinfunction "K_2") (pintype "passive"))
      (node (ref "LED18") (pin "2") (pinfunction "K_2") (pintype "passive"))
      (node (ref "LED2") (pin "2") (pinfunction "K_2") (pintype "passive"))
      (node (ref "LED26") (pin "2") (pinfunction "K_2") (pintype "passive"))
      (node (ref "LED34") (pin "2") (pinfunction "K_2") (pintype "passive"))
      (node (ref "LED42") (pin "2") (pinfunction "K_2") (pintype "passive"))
      (node (ref "LED50") (pin "2") (pinfunction "K_2") (pintype "passive"))
      (node (ref "LED58") (pin "2") (pinfunction "K_2") (pintype "passive"))
      (node (ref "R2") (pin "2") (pinfunction "2_2") (pintype "passive"))
    )
    (net (code "24") (name "Net-(LED11-K)") (class "Default")
      (node (ref "LED11") (pin "2") (pinfunction "K_2") (pintype "passive"))
      (node (ref "LED19") (pin "2") (pinfunction "K_2") (pintype "passive"))
      (node (ref "LED27") (pin "2") (pinfunction "K_2") (pintype "passive"))
      (node (ref "LED3") (pin "2") (pinfunction "K_2") (pintype "passive"))
      (node (ref "LED35") (pin "2") (pinfunction "K_2") (pintype "passive"))
      (node (ref "LED43") (pin "2") (pinfunction "K_2") (pintype "passive"))
      (node (ref "LED51") (pin "2") (pinfunction "K_2") (pintype "passive"))
      (node (ref "LED59") (pin "2") (pinfunction "K_2") (pintype "passive"))
      (node (ref "R3") (pin "2") (pinfunction "2_2") (pintype "passive"))
    )
    (net (code "25") (name "Net-(LED12-K)") (class "Default")
      (node (ref "LED12") (pin "2") (pinfunction "K_2") (pintype "passive"))
      (node (ref "LED20") (pin "2") (pinfunction "K_2") (pintype "passive"))
      (node (ref "LED28") (pin "2") (pinfunction "K_2") (pintype "passive"))
      (node (ref "LED36") (pin "2") (pinfunction "K_2") (pintype "passive"))
      (node (ref "LED4") (pin "2") (pinfunction "K_2") (pintype "passive"))
      (node (ref "LED44") (pin "2") (pinfunction "K_2") (pintype "passive"))
      (node (ref "LED52") (pin "2") (pinfunction "K_2") (pintype "passive"))
      (node (ref "LED60") (pin "2") (pinfunction "K_2") (pintype "passive"))
      (node (ref "R4") (pin "2") (pinfunction "2_2") (pintype "passive"))
    )
    (net (code "26") (name "Net-(LED13-K)") (class "Default")
      (node (ref "LED13") (pin "2") (pinfunction "K_2") (pintype "passive"))
      (node (ref "LED21") (pin "2") (pinfunction "K_2") (pintype "passive"))
      (node (ref "LED29") (pin "2") (pinfunction "K_2") (pintype "passive"))
      (node (ref "LED37") (pin "2") (pinfunction "K_2") (pintype "passive"))
      (node (ref "LED45") (pin "2") (pinfunction "K_2") (pintype "passive"))
      (node (ref "LED5") (pin "2") (pinfunction "K_2") (pintype "passive"))
      (node (ref "LED53") (pin "2") (pinfunction "K_2") (pintype "passive"))
      (node (ref "LED61") (pin "2") (pinfunction "K_2") (pintype "passive"))
      (node (ref "R5") (pin "2") (pinfunction "2_2") (pintype "passive"))
    )
    (net (code "27") (name "Net-(LED14-K)") (class "Default")
      (node (ref "LED14") (pin "2") (pinfunction "K_2") (pintype "passive"))
      (node (ref "LED22") (pin "2") (pinfunction "K_2") (pintype "passive"))
      (node (ref "LED30") (pin "2") (pinfunction "K_2") (pintype "passive"))
      (node (ref "LED38") (pin "2") (pinfunction "K_2") (pintype "passive"))
      (node (ref "LED46") (pin "2") (pinfunction "K_2") (pintype "passive"))
      (node (ref "LED54") (pin "2") (pinfunction "K_2") (pintype "passive"))
      (node (ref "LED6") (pin "2") (pinfunction "K_2") (pintype "passive"))
      (node (ref "LED62") (pin "2") (pinfunction "K_2") (pintype "passive"))
      (node (ref "R6") (pin "2") (pinfunction "2_2") (pintype "passive"))
    )
    (net (code "28") (name "Net-(LED15-K)") (class "Default")
      (node (ref "LED15") (pin "2") (pinfunction "K_2") (pintype "passive"))
      (node (ref "LED23") (pin "2") (pinfunction "K_2") (pintype "passive"))
      (node (ref "LED31") (pin "2") (pinfunction "K_2") (pintype "passive"))
      (node (ref "LED39") (pin "2") (pinfunction "K_2") (pintype "passive"))
      (node (ref "LED47") (pin "2") (pinfunction "K_2") (pintype "passive"))
      (node (ref "LED55") (pin "2") (pinfunction "K_2") (pintype "passive"))
      (node (ref "LED63") (pin "2") (pinfunction "K_2") (pintype "passive"))
      (node (ref "LED7") (pin "2") (pinfunction "K_2") (pintype "passive"))
      (node (ref "R7") (pin "2") (pinfunction "2_2") (pintype "passive"))
    )
    (net (code "29") (name "Net-(LED16-K)") (class "Default")
      (node (ref "LED16") (pin "2") (pinfunction "K_2") (pintype "passive"))
      (node (ref "LED24") (pin "2") (pinfunction "K_2") (pintype "passive"))
      (node (ref "LED32") (pin "2") (pinfunction "K_2") (pintype "passive"))
      (node (ref "LED40") (pin "2") (pinfunction "K_2") (pintype "passive"))
      (node (ref "LED48") (pin "2") (pinfunction "K_2") (pintype "passive"))
      (node (ref "LED56") (pin "2") (pinfunction "K_2") (pintype "passive"))
      (node (ref "LED64") (pin "2") (pinfunction "K_2") (pintype "passive"))
      (node (ref "LED8") (pin "2") (pinfunction "K_2") (pintype "passive"))
      (node (ref "R8") (pin "2") (pinfunction "2_2") (pintype "passive"))
    )
    (net (code "30") (name "VCC") (class "Default")
      (node (ref "BO1") (pin "7") (pinfunction "VBUS_7") (pintype "power_in"))
      (node (ref "BO2") (pin "18") (pinfunction "AVCC_18") (pintype "power_in"))
      (node (ref "BO2") (pin "7") (pinfunction "VCC_7") (pintype "power_in"))
      (node (ref "C1") (pin "1") (pinfunction "1_1") (pintype "passive"))
      (node (ref "C2") (pin "1") (pinfunction "1_1") (pintype "passive"))
      (node (ref "TP2") (pin "1") (pinfunction "1_1") (pintype "passive"))
      (node (ref "U1") (pin "16") (pinfunction "Vcc_16") (pintype "passive"))
    )
    (net (code "31") (name "unconnected-(BO1-CC1-Pad5)") (class "Default")
      (node (ref "BO1") (pin "5") (pinfunction "CC1_5") (pintype "bidirectional"))
    )
    (net (code "32") (name "unconnected-(BO1-CC2-Pad1)") (class "Default")
      (node (ref "BO1") (pin "1") (pinfunction "CC2_1") (pintype "bidirectional"))
    )
    (net (code "33") (name "unconnected-(BO1-D+-Pad3)") (class "Default")
      (node (ref "BO1") (pin "3") (pinfunction "D+_3") (pintype "bidirectional"))
    )
    (net (code "34") (name "unconnected-(BO1-D--Pad4)") (class "Default")
      (node (ref "BO1") (pin "4") (pinfunction "D-_4") (pintype "bidirectional"))
    )
    (net (code "35") (name "unconnected-(BO1-SBU1-Pad2)") (class "Default")
      (node (ref "BO1") (pin "2") (pinfunction "SBU1_2") (pintype "bidirectional"))
    )
    (net (code "36") (name "unconnected-(BO1-SBU2-Pad6)") (class "Default")
      (node (ref "BO1") (pin "6") (pinfunction "SBU2_6") (pintype "bidirectional"))
    )
    (net (code "37") (name "unconnected-(BO2-AREF-Pad19)") (class "Default")
      (node (ref "BO2") (pin "19") (pinfunction "AREF_19") (pintype "input"))
    )
    (net (code "38") (name "unconnected-(BO2-PB3-Pad15)") (class "Default")
      (node (ref "BO2") (pin "15") (pinfunction "PB3_15") (pintype "bidirectional"))
    )
    (net (code "39") (name "unconnected-(BO2-PB4-Pad16)") (class "Default")
      (node (ref "BO2") (pin "16") (pinfunction "PB4_16") (pintype "bidirectional"))
    )
    (net (code "40") (name "unconnected-(BO2-PB5-Pad17)") (class "Default")
      (node (ref "BO2") (pin "17") (pinfunction "PB5_17") (pintype "bidirectional"))
    )
    (net (code "41") (name "unconnected-(BO2-PC1-Pad22)") (class "Default")
      (node (ref "BO2") (pin "22") (pinfunction "PC1_22") (pintype "bidirectional"))
    )
    (net (code "42") (name "unconnected-(BO2-PC2-Pad23)") (class "Default")
      (node (ref "BO2") (pin "23") (pinfunction "PC2_23") (pintype "bidirectional"))
    )
    (net (code "43") (name "unconnected-(BO2-PC3-Pad24)") (class "Default")
      (node (ref "BO2") (pin "24") (pinfunction "PC3_24") (pintype "bidirectional"))
    )
    (net (code "44") (name "unconnected-(BO2-PC4-Pad25)") (class "Default")
      (node (ref "BO2") (pin "25") (pinfunction "PC4_25") (pintype "bidirectional"))
    )
    (net (code "45") (name "unconnected-(BO2-PC5-Pad26)") (class "Default")
      (node (ref "BO2") (pin "26") (pinfunction "PC5_26") (pintype "bidirectional"))
    )
    (net (code "46") (name "unconnected-(BO2-PC6-Pad1)") (class "Default")
      (node (ref "BO2") (pin "1") (pinfunction "PC6_1") (pintype "bidirectional"))
    )
    (net (code "47") (name "unconnected-(U1-OE-Pad7)") (class "Default")
      (node (ref "U1") (pin "7") (pinfunction "OE_7") (pintype "passive"))
    )
  )
)
